# LoRa_PCB.net
KiCad netlist of a schematic drawn in Altium Designer
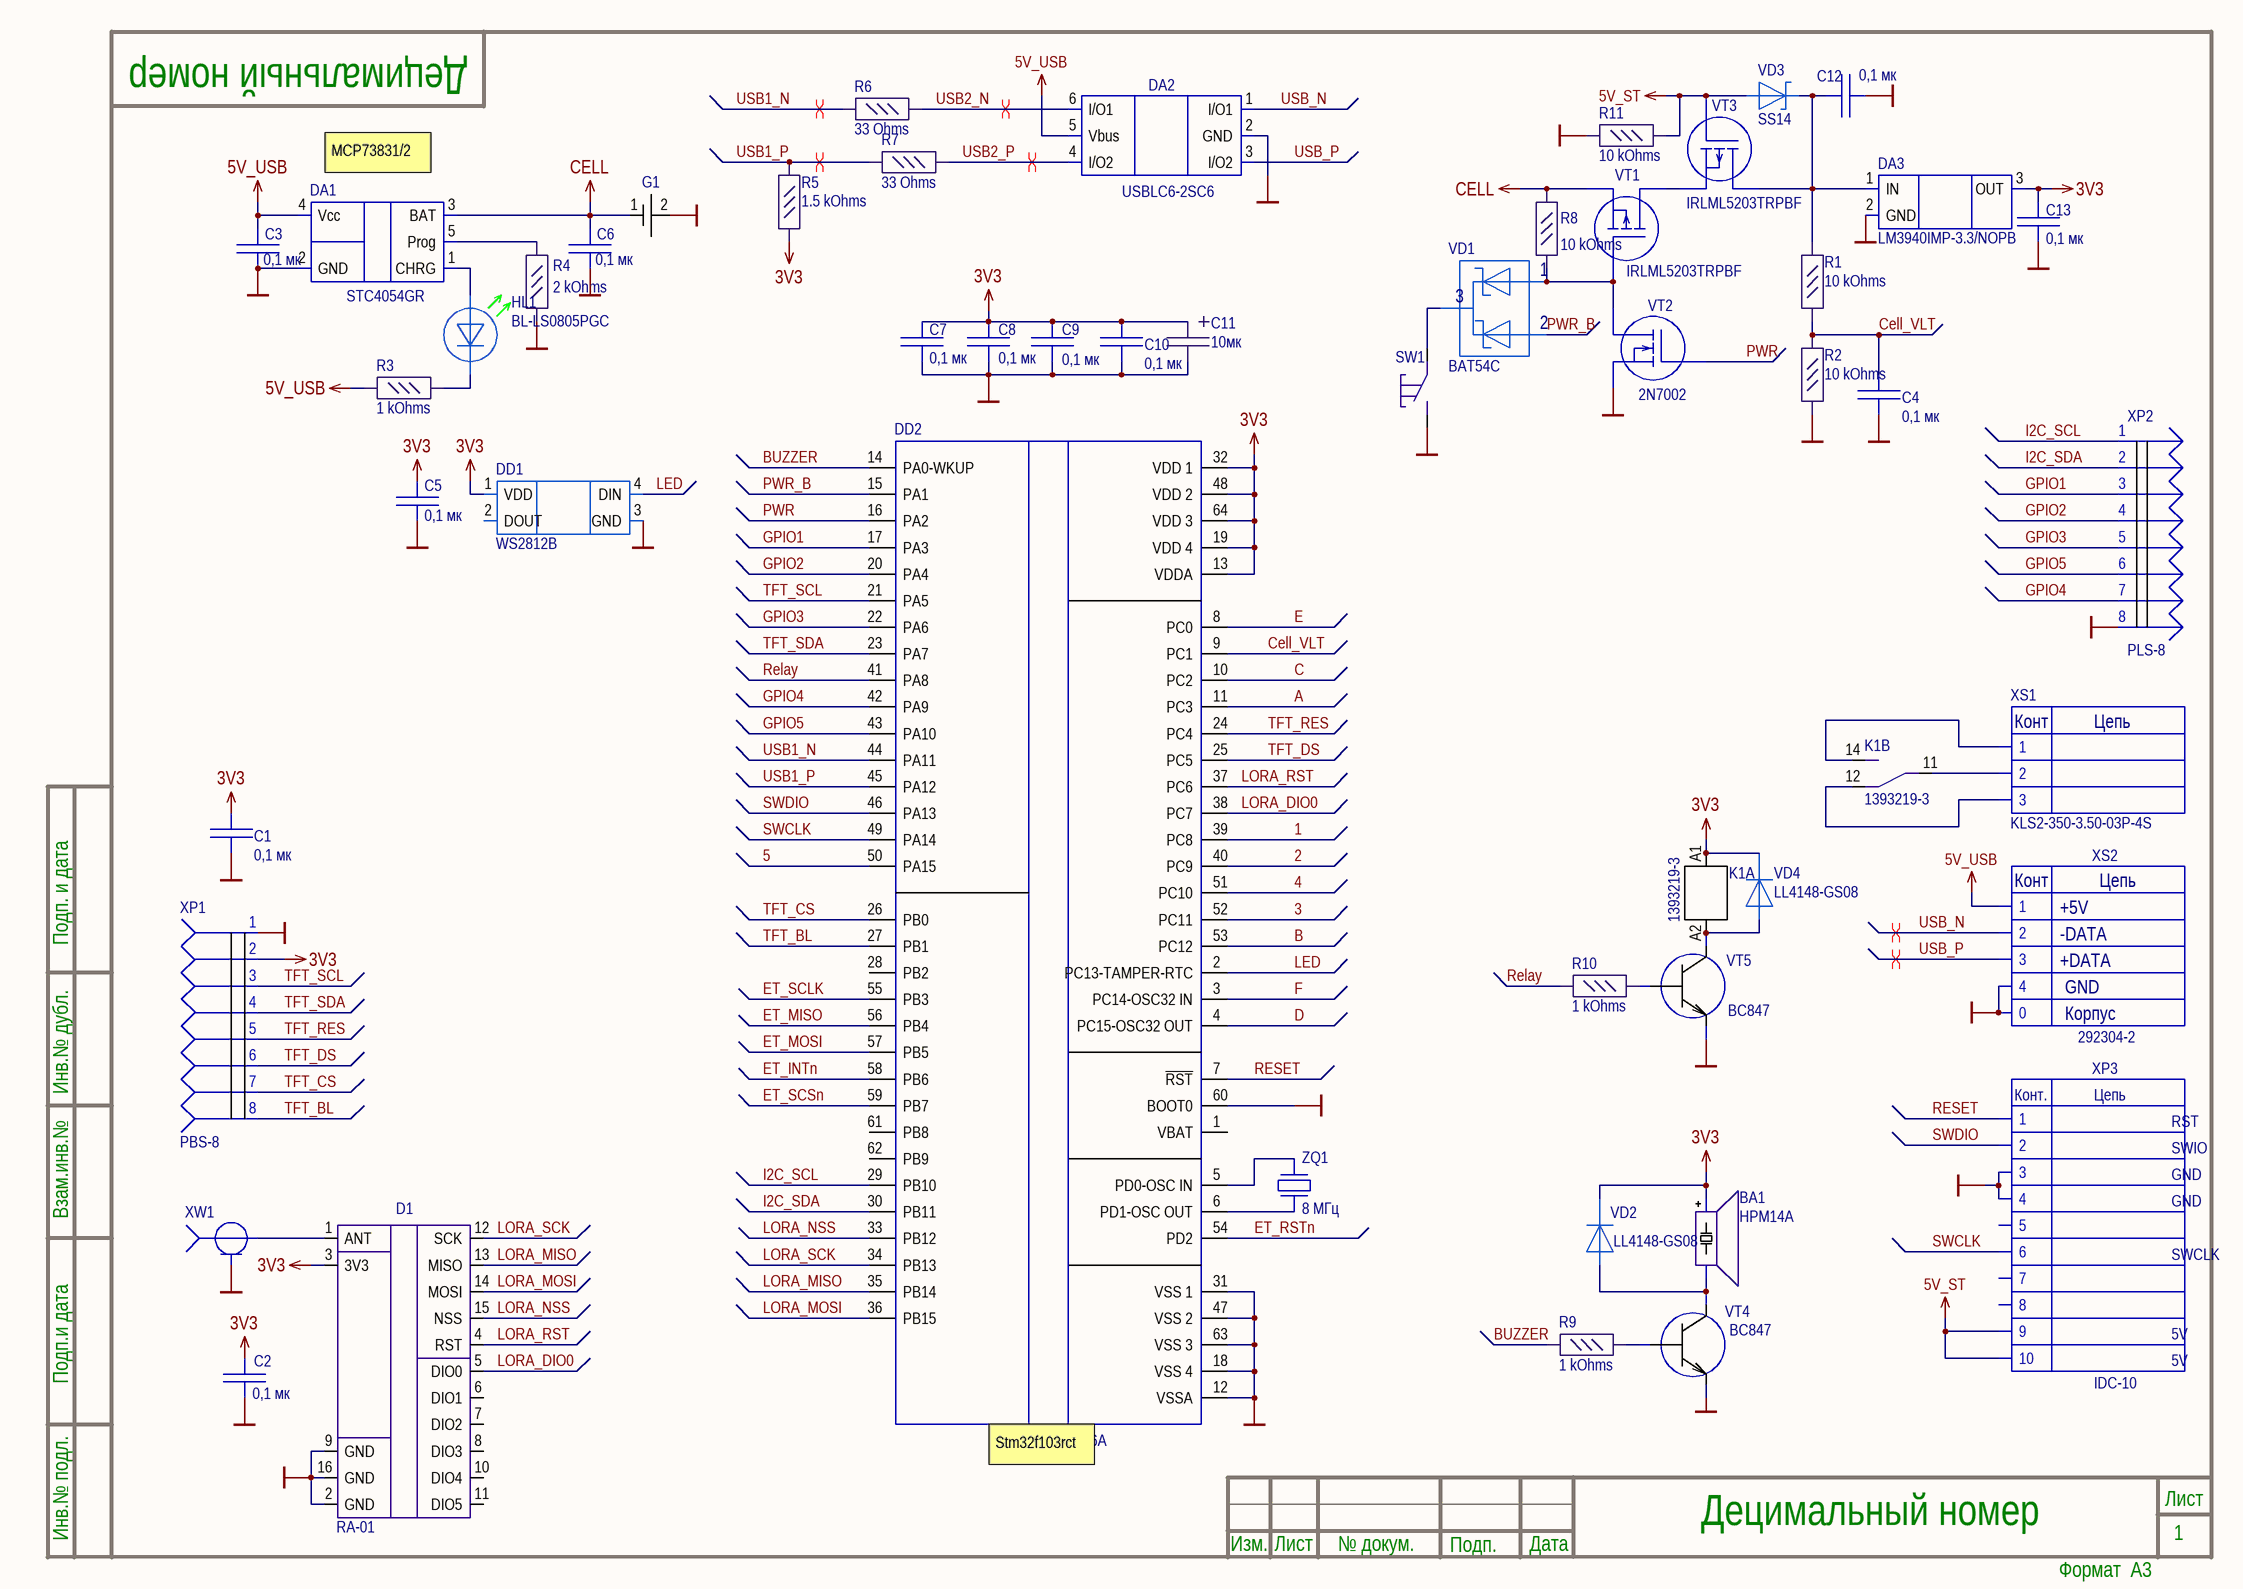
[diagram p0: LoRa_PCB.SchDoc]

(export (version "E")
  (design (tool "Eeschema 10.0.6"))
  (components
    (comp (ref "BA1") (value "HPM14A") (footprint "HPM14A") (libsource (lib "8. Other") (part "HPM14A")))
    (comp (ref "C1") (value "0,1 мк") (footprint "C_0805") (libsource (lib "RK3AZB") (part "C_0805")))
    (comp (ref "C2") (value "0,1 мк") (footprint "C_0805") (libsource (lib "RK3AZB") (part "C_0805")))
    (comp (ref "C3") (value "0,1 мк") (footprint "C_0805") (libsource (lib "2.Capasitors") (part "C_0805")))
    (comp (ref "C4") (value "0,1 мк") (footprint "C_0805") (libsource (lib "RK3AZB") (part "C_0805")))
    (comp (ref "C5") (value "0,1 мк") (footprint "C_0805") (libsource (lib "RK3AZB") (part "C_0805")))
    (comp (ref "C6") (value "0,1 мк") (footprint "C_0805") (libsource (lib "2.Capasitors") (part "C_0805")))
    (comp (ref "C7") (value "0,1 мк") (footprint "C_0805") (libsource (lib "2.Capasitors") (part "C_0805")))
    (comp (ref "C8") (value "0,1 мк") (footprint "C_0805") (libsource (lib "2.Capasitors") (part "C_0805")))
    (comp (ref "C9") (value "0,1 мк") (footprint "C_0805") (libsource (lib "2.Capasitors") (part "C_0805")))
    (comp (ref "C10") (value "0,1 мк") (footprint "C_0805") (libsource (lib "2.Capasitors") (part "C_0805")))
    (comp (ref "C11")
      (value "10мк")
      (footprint "D_CASE")
      (description "CAP TANT 10UF 10% 35V 2917")
      (fields (field (name "PART NUMBER") "T491D106K035AT") (field (name "MANUFACTURER") "KEMET"))
      (libsource (lib "Database_Lib") (part "Tantalum Capacitor"))
    )
    (comp (ref "C12") (value "0,1 мк") (footprint "C_0805") (libsource (lib "2.Capasitors") (part "C_0805")))
    (comp (ref "C13") (value "0,1 мк") (footprint "C_0805") (libsource (lib "2.Capasitors") (part "C_0805")))
    (comp (ref "D1")
      (value "RA-01")
      (footprint "RA-02")
      (description "LoRa modem")
      (libsource (lib "8. Other") (part "RA-01"))
    )
    (comp (ref "DA1")
      (value "STC4054GR")
      (footprint "TSOT23-5L")
      (description "Контроллер заряда Lion батарей")
      (libsource (lib "6.Chips") (part "STC4054GR"))
    )
    (comp (ref "DA2")
      (value "USBLC6-2SC6")
      (footprint "SOT-23-6")
      (libsource (lib "2. Chips") (part "USBLC6-2SC6"))
    )
    (comp (ref "DA3")
      (value "LM3940IMP-3.3/NOPB")
      (footprint "SOT223")
      (description "Регулятор с малым падением напряжения, преобразование 5В в 3.3В/ 1А")
      (libsource (lib "6.Chips") (part "LM3940IMP-3.3/NOPB"))
    )
    (comp (ref "DD1") (value "WS2812B") (footprint "WS2812B") (libsource (lib "4.Diodes") (part "WS2812B")))
    (comp (ref "DD2")
      (value "STM32F103R6T6A")
      (footprint "LQFP64")
      (description "32-Bit 72MHz 32KB (32K x 8) FLASH 64-LQFP")
      (libsource (lib "6.Chips") (part "STM32F103R6T6A"))
    )
    (comp (ref "G1")
      (value "12BHC186P1-GR")
      (footprint "12BHC186P1-GR")
      (description "Батарейный отсек 1x18650")
      (libsource (lib "8. Other") (part "12BHC186P1-GR"))
    )
    (comp (ref "HL1")
      (value "BL-LS0805PGC")
      (footprint "LED_0805_GREEN")
      (libsource (lib "4.Diodes") (part "BL-LS0805PGC"))
    )
    (comp (ref "K1")
      (value "1393219-3")
      (footprint "1393219-3")
      (description "Реле 5VDC")
      (libsource (lib "9.Commutation") (part "1393219-3"))
    )
    (comp (ref "R1")
      (value "10 kOhms")
      (footprint "R_0805")
      (description "RES SMD 10K OHM 1% 1/8W 0805")
      (fields (field (name "PART NUMBER") "CR0805-FX-1002ELF") (field (name "MANUFACTURER") "Bourns Inc."))
      (libsource (lib "Database_Lib") (part "Resistor"))
    )
    (comp (ref "R2")
      (value "10 kOhms")
      (footprint "R_0805")
      (description "RES SMD 10K OHM 1% 1/8W 0805")
      (fields (field (name "PART NUMBER") "CR0805-FX-1002ELF") (field (name "MANUFACTURER") "Bourns Inc."))
      (libsource (lib "Database_Lib") (part "Resistor"))
    )
    (comp (ref "R3")
      (value "1 kOhms")
      (footprint "R_0805")
      (description "RES SMD 1K OHM 1% 1/8W 0805")
      (fields (field (name "PART NUMBER") "CR0805-FX-1001ELF") (field (name "MANUFACTURER") "Bourns Inc."))
      (libsource (lib "Database_Lib") (part "Resistor"))
    )
    (comp (ref "R4")
      (value "2 kOhms")
      (footprint "R_0805")
      (description "RES SMD 2K OHM 1% 1/8W 0805")
      (fields (field (name "PART NUMBER") "CR0805-FX-2001ELF") (field (name "MANUFACTURER") "Bourns Inc."))
      (libsource (lib "Database_Lib") (part "Resistor"))
    )
    (comp (ref "R5")
      (value "1.5 kOhms")
      (footprint "R_0805")
      (description "RES SMD 1.5K OHM 1% 1/8W 0805")
      (fields (field (name "PART NUMBER") "CR0805-FX-1501ELF") (field (name "MANUFACTURER") "Bourns Inc."))
      (libsource (lib "Database_Lib") (part "Resistor"))
    )
    (comp (ref "R6")
      (value "33 Ohms")
      (footprint "R_0805")
      (description "RES SMD 33 OHM 1% 1/8W 0805")
      (fields (field (name "PART NUMBER") "CR0805-FX-33R0ELF") (field (name "MANUFACTURER") "Bourns Inc."))
      (libsource (lib "Database_Lib") (part "Resistor"))
    )
    (comp (ref "R7")
      (value "33 Ohms")
      (footprint "R_0805")
      (description "RES SMD 33 OHM 1% 1/8W 0805")
      (fields (field (name "PART NUMBER") "CR0805-FX-33R0ELF") (field (name "MANUFACTURER") "Bourns Inc."))
      (libsource (lib "Database_Lib") (part "Resistor"))
    )
    (comp (ref "R8")
      (value "10 kOhms")
      (footprint "R_0805")
      (description "RES SMD 10K OHM 1% 1/8W 0805")
      (fields (field (name "PART NUMBER") "CR0805-FX-1002ELF") (field (name "MANUFACTURER") "Bourns Inc."))
      (libsource (lib "Database_Lib") (part "Resistor"))
    )
    (comp (ref "R9")
      (value "1 kOhms")
      (footprint "R_0805")
      (description "RES SMD 1K OHM 1% 1/8W 0805")
      (fields (field (name "PART NUMBER") "CR0805-FX-1001ELF") (field (name "MANUFACTURER") "Bourns Inc."))
      (libsource (lib "Database_Lib") (part "Resistor"))
    )
    (comp (ref "R10")
      (value "1 kOhms")
      (footprint "R_0805")
      (description "RES SMD 1K OHM 1% 1/8W 0805")
      (fields (field (name "PART NUMBER") "CR0805-FX-1001ELF") (field (name "MANUFACTURER") "Bourns Inc."))
      (libsource (lib "Database_Lib") (part "Resistor"))
    )
    (comp (ref "R11")
      (value "10 kOhms")
      (footprint "R_0805")
      (description "RES SMD 10K OHM 1% 1/8W 0805")
      (fields (field (name "PART NUMBER") "CR0805-FX-1002ELF") (field (name "MANUFACTURER") "Bourns Inc."))
      (libsource (lib "Database_Lib") (part "Resistor"))
    )
    (comp (ref "SW1")
      (value "KLS7-TS6604")
      (footprint "KLS7-TS6604-5.0-180-B")
      (libsource (lib "9.Commutation") (part "KLS7-TS6604"))
    )
    (comp (ref "VD1")
      (value "BAT54C")
      (footprint "SOT23")
      (description "Диод Шоттки, 2 диода, общий катод, 30В, 0.2А [SOT-23]")
      (libsource (lib "4.Diodes") (part "BAT54C"))
    )
    (comp (ref "VD2")
      (value "LL4148-GS08")
      (footprint "SOD-80")
      (description "Диод")
      (libsource (lib "RK3AZB") (part "LL4148-GS08"))
    )
    (comp (ref "VD3") (value "SS14") (footprint "DO-214AC") (libsource (lib "4.Diodes") (part "SS14")))
    (comp (ref "VD4")
      (value "LL4148-GS08")
      (footprint "SOD-80")
      (description "Диод")
      (libsource (lib "RK3AZB") (part "LL4148-GS08"))
    )
    (comp (ref "VT1")
      (value "IRLML5203TRPBF")
      (footprint "SOT23")
      (description "Транзистор, P-канал 30В 3A logic")
      (libsource (lib "5.Transistors") (part "IRLML5203TRPBF"))
    )
    (comp (ref "VT2")
      (value "2N7002")
      (footprint "SOT23")
      (description "N-ch MFE transistor")
      (libsource (lib "5.Transistors") (part "2N7002"))
    )
    (comp (ref "VT3")
      (value "IRLML5203TRPBF")
      (footprint "SOT23")
      (description "Транзистор, P-канал 30В 3A logic")
      (libsource (lib "5.Transistors") (part "IRLML5203TRPBF"))
    )
    (comp (ref "VT4") (value "BC847") (footprint "SOT23") (libsource (lib "4. Transistors") (part "BC847")))
    (comp (ref "VT5") (value "BC847") (footprint "SOT23") (libsource (lib "RK3AZB") (part "BC847")))
    (comp (ref "XP1") (value "PBS-8") (footprint "PBS-8") (libsource (lib "7.Connectors") (part "PBS-8")))
    (comp (ref "XP2") (value "PLS-8") (footprint "PLS-8") (libsource (lib "7.Connectors") (part "PLS-8")))
    (comp (ref "XP3") (value "IDC-10") (footprint "IDC-10") (libsource (lib "7. Connectors") (part "IDC-10")))
    (comp (ref "XS1")
      (value "KLS2-350-3.50-03P-4S")
      (footprint "KLS2-350-3.50-03P-4S")
      (description "Клеммник, 3-контактный, 3.5мм")
      (libsource (lib "7. Connectors") (part "KLS2-350-3.50-03P-4S"))
    )
    (comp (ref "XS2")
      (value "292304-2")
      (footprint "USB-B")
      (libsource (lib "7.Connectors") (part "292304-2"))
    )
    (comp (ref "XW1")
      (value "HYR-1139-RP")
      (footprint "SMA (HYR1139)")
      (libsource (lib "7. Connectors") (part "HYR-1139-RP"))
    )
    (comp (ref "ZQ1")
      (value "8 МГц")
      (footprint "MJ CRYSTAL")
      (libsource (lib "8.Resonarors") (part "NX5032GA-8MHz"))
    )
  )
  (nets
    (net (code "1") (name "/1") (class "Default")
      (node (ref "DD2") (pin "39") (pinfunction "PC8_39") (pintype "passive"))
    )
    (net (code "2") (name "/2") (class "Default")
      (node (ref "DD2") (pin "40") (pinfunction "PC9_40") (pintype "passive"))
    )
    (net (code "3") (name "/3") (class "Default")
      (node (ref "DD2") (pin "52") (pinfunction "PC11_52") (pintype "passive"))
    )
    (net (code "4") (name "/4") (class "Default")
      (node (ref "DD2") (pin "51") (pinfunction "PC10_51") (pintype "passive"))
    )
    (net (code "5") (name "/5") (class "Default")
      (node (ref "DD2") (pin "50") (pinfunction "PA15_50") (pintype "passive"))
    )
    (net (code "6") (name "/A") (class "Default")
      (node (ref "DD2") (pin "11") (pinfunction "PC3_11") (pintype "passive"))
    )
    (net (code "7") (name "/B") (class "Default")
      (node (ref "DD2") (pin "53") (pinfunction "PC12_53") (pintype "passive"))
    )
    (net (code "8") (name "/BUZZER") (class "Default")
      (node (ref "DD2") (pin "14") (pinfunction "PA0-WKUP_14") (pintype "passive"))
      (node (ref "R9") (pin "2") (pinfunction "2_2") (pintype "passive"))
    )
    (net (code "9") (name "/C") (class "Default")
      (node (ref "DD2") (pin "10") (pinfunction "PC2_10") (pintype "passive"))
    )
    (net (code "10") (name "/Cell_VLT") (class "Default")
      (node (ref "C4") (pin "2") (pinfunction "2_2") (pintype "passive"))
      (node (ref "DD2") (pin "9") (pinfunction "PC1_9") (pintype "passive"))
      (node (ref "R1") (pin "2") (pinfunction "2_2") (pintype "passive"))
      (node (ref "R2") (pin "1") (pinfunction "1_1") (pintype "passive"))
    )
    (net (code "11") (name "/D") (class "Default")
      (node (ref "DD2") (pin "4") (pinfunction "PC15-OSC32_OUT_4") (pintype "passive"))
    )
    (net (code "12") (name "/E") (class "Default")
      (node (ref "DD2") (pin "8") (pinfunction "PC0_8") (pintype "passive"))
    )
    (net (code "13") (name "/ET_INTn") (class "Default")
      (node (ref "DD2") (pin "58") (pinfunction "PB6_58") (pintype "passive"))
    )
    (net (code "14") (name "/ET_MISO") (class "Default")
      (node (ref "DD2") (pin "56") (pinfunction "PB4_56") (pintype "passive"))
    )
    (net (code "15") (name "/ET_MOSI") (class "Default")
      (node (ref "DD2") (pin "57") (pinfunction "PB5_57") (pintype "passive"))
    )
    (net (code "16") (name "/ET_RSTn") (class "Default")
      (node (ref "DD2") (pin "54") (pinfunction "PD2_54") (pintype "passive"))
    )
    (net (code "17") (name "/ET_SCLK") (class "Default")
      (node (ref "DD2") (pin "55") (pinfunction "PB3_55") (pintype "passive"))
    )
    (net (code "18") (name "/ET_SCSn") (class "Default")
      (node (ref "DD2") (pin "59") (pinfunction "PB7_59") (pintype "passive"))
    )
    (net (code "19") (name "/F") (class "Default")
      (node (ref "DD2") (pin "3") (pinfunction "PC14-OSC32_IN_3") (pintype "passive"))
    )
    (net (code "20") (name "/GPIO1") (class "Default")
      (node (ref "DD2") (pin "17") (pinfunction "PA3_17") (pintype "passive"))
      (node (ref "XP2") (pin "3") (pinfunction "3_3") (pintype "passive"))
    )
    (net (code "21") (name "/GPIO2") (class "Default")
      (node (ref "DD2") (pin "20") (pinfunction "PA4_20") (pintype "passive"))
      (node (ref "XP2") (pin "4") (pinfunction "4_4") (pintype "passive"))
    )
    (net (code "22") (name "/GPIO3") (class "Default")
      (node (ref "DD2") (pin "22") (pinfunction "PA6_22") (pintype "passive"))
      (node (ref "XP2") (pin "5") (pinfunction "5_5") (pintype "passive"))
    )
    (net (code "23") (name "/GPIO4") (class "Default")
      (node (ref "DD2") (pin "42") (pinfunction "PA9_42") (pintype "passive"))
      (node (ref "XP2") (pin "7") (pinfunction "7_7") (pintype "passive"))
    )
    (net (code "24") (name "/GPIO5") (class "Default")
      (node (ref "DD2") (pin "43") (pinfunction "PA10_43") (pintype "passive"))
      (node (ref "XP2") (pin "6") (pinfunction "6_6") (pintype "passive"))
    )
    (net (code "25") (name "/I2C_SCL") (class "Default")
      (node (ref "DD2") (pin "29") (pinfunction "PB10_29") (pintype "passive"))
      (node (ref "XP2") (pin "1") (pinfunction "1_1") (pintype "passive"))
    )
    (net (code "26") (name "/I2C_SDA") (class "Default")
      (node (ref "DD2") (pin "30") (pinfunction "PB11_30") (pintype "passive"))
      (node (ref "XP2") (pin "2") (pinfunction "2_2") (pintype "passive"))
    )
    (net (code "27") (name "/LED") (class "Default")
      (node (ref "DD1") (pin "4") (pinfunction "DIN_4") (pintype "passive"))
      (node (ref "DD2") (pin "2") (pinfunction "PC13-TAMPER-RTC_2") (pintype "passive"))
    )
    (net (code "28") (name "/LORA_DIO0") (class "Default")
      (node (ref "D1") (pin "5") (pinfunction "DIO0_5") (pintype "passive"))
      (node (ref "DD2") (pin "38") (pinfunction "PC7_38") (pintype "passive"))
    )
    (net (code "29") (name "/LORA_MISO") (class "Default")
      (node (ref "D1") (pin "13") (pinfunction "MISO_13") (pintype "passive"))
      (node (ref "DD2") (pin "35") (pinfunction "PB14_35") (pintype "passive"))
    )
    (net (code "30") (name "/LORA_MOSI") (class "Default")
      (node (ref "D1") (pin "14") (pinfunction "MOSI_14") (pintype "passive"))
      (node (ref "DD2") (pin "36") (pinfunction "PB15_36") (pintype "passive"))
    )
    (net (code "31") (name "/LORA_NSS") (class "Default")
      (node (ref "D1") (pin "15") (pinfunction "NSS_15") (pintype "passive"))
      (node (ref "DD2") (pin "33") (pinfunction "PB12_33") (pintype "passive"))
    )
    (net (code "32") (name "/LORA_RST") (class "Default")
      (node (ref "D1") (pin "4") (pinfunction "RST_4") (pintype "passive"))
      (node (ref "DD2") (pin "37") (pinfunction "PC6_37") (pintype "passive"))
    )
    (net (code "33") (name "/LORA_SCK") (class "Default")
      (node (ref "D1") (pin "12") (pinfunction "SCK_12") (pintype "passive"))
      (node (ref "DD2") (pin "34") (pinfunction "PB13_34") (pintype "passive"))
    )
    (net (code "34") (name "/PWR") (class "Default")
      (node (ref "DD2") (pin "16") (pinfunction "PA2_16") (pintype "passive"))
      (node (ref "VT2") (pin "1") (pinfunction "G_1") (pintype "passive"))
    )
    (net (code "35") (name "/PWR_B") (class "Default")
      (node (ref "DD2") (pin "15") (pinfunction "PA1_15") (pintype "passive"))
      (node (ref "VD1") (pin "2") (pinfunction "C2_2") (pintype "passive"))
    )
    (net (code "36") (name "/RESET") (class "Default")
      (node (ref "DD2") (pin "7") (pinfunction "~{RST}_7") (pintype "passive"))
      (node (ref "XP3") (pin "1") (pinfunction "1_1") (pintype "passive"))
    )
    (net (code "37") (name "/Relay") (class "Default")
      (node (ref "DD2") (pin "41") (pinfunction "PA8_41") (pintype "passive"))
      (node (ref "R10") (pin "2") (pinfunction "2_2") (pintype "passive"))
    )
    (net (code "38") (name "/SWCLK") (class "Default")
      (node (ref "DD2") (pin "49") (pinfunction "PA14_49") (pintype "passive"))
      (node (ref "XP3") (pin "6") (pinfunction "6_6") (pintype "passive"))
    )
    (net (code "39") (name "/SWDIO") (class "Default")
      (node (ref "DD2") (pin "46") (pinfunction "PA13_46") (pintype "passive"))
      (node (ref "XP3") (pin "2") (pinfunction "2_2") (pintype "passive"))
    )
    (net (code "40") (name "/TFT_BL") (class "Default")
      (node (ref "DD2") (pin "27") (pinfunction "PB1_27") (pintype "passive"))
      (node (ref "XP1") (pin "8") (pinfunction "8_8") (pintype "passive"))
    )
    (net (code "41") (name "/TFT_CS") (class "Default")
      (node (ref "DD2") (pin "26") (pinfunction "PB0_26") (pintype "passive"))
      (node (ref "XP1") (pin "7") (pinfunction "7_7") (pintype "passive"))
    )
    (net (code "42") (name "/TFT_DS") (class "Default")
      (node (ref "DD2") (pin "25") (pinfunction "PC5_25") (pintype "passive"))
      (node (ref "XP1") (pin "6") (pinfunction "6_6") (pintype "passive"))
    )
    (net (code "43") (name "/TFT_RES") (class "Default")
      (node (ref "DD2") (pin "24") (pinfunction "PC4_24") (pintype "passive"))
      (node (ref "XP1") (pin "5") (pinfunction "5_5") (pintype "passive"))
    )
    (net (code "44") (name "/TFT_SCL") (class "Default")
      (node (ref "DD2") (pin "21") (pinfunction "PA5_21") (pintype "passive"))
      (node (ref "XP1") (pin "3") (pinfunction "3_3") (pintype "passive"))
    )
    (net (code "45") (name "/TFT_SDA") (class "Default")
      (node (ref "DD2") (pin "23") (pinfunction "PA7_23") (pintype "passive"))
      (node (ref "XP1") (pin "4") (pinfunction "4_4") (pintype "passive"))
    )
    (net (code "46") (name "/USB1_N") (class "Default")
      (node (ref "DD2") (pin "44") (pinfunction "PA11_44") (pintype "passive"))
      (node (ref "R6") (pin "1") (pinfunction "1_1") (pintype "passive"))
    )
    (net (code "47") (name "/USB1_P") (class "Default")
      (node (ref "DD2") (pin "45") (pinfunction "PA12_45") (pintype "passive"))
      (node (ref "R5") (pin "2") (pinfunction "2_2") (pintype "passive"))
      (node (ref "R7") (pin "1") (pinfunction "1_1") (pintype "passive"))
    )
    (net (code "48") (name "/USB2_N") (class "Default")
      (node (ref "DA2") (pin "6") (pinfunction "I/O1_6") (pintype "passive"))
      (node (ref "R6") (pin "2") (pinfunction "2_2") (pintype "passive"))
    )
    (net (code "49") (name "/USB2_P") (class "Default")
      (node (ref "DA2") (pin "4") (pinfunction "I/O2_4") (pintype "passive"))
      (node (ref "R7") (pin "2") (pinfunction "2_2") (pintype "passive"))
    )
    (net (code "50") (name "/USB_N") (class "Default")
      (node (ref "DA2") (pin "1") (pinfunction "I/O1_1") (pintype "passive"))
      (node (ref "XS2") (pin "2") (pinfunction "2_2") (pintype "passive"))
    )
    (net (code "51") (name "/USB_P") (class "Default")
      (node (ref "DA2") (pin "3") (pinfunction "I/O2_3") (pintype "passive"))
      (node (ref "XS2") (pin "3") (pinfunction "3_3") (pintype "passive"))
    )
    (net (code "52") (name "3V3") (class "Default")
      (node (ref "BA1") (pin "1") (pinfunction "1_1") (pintype "passive"))
      (node (ref "C1") (pin "2") (pinfunction "2_2") (pintype "passive"))
      (node (ref "C10") (pin "2") (pinfunction "2_2") (pintype "passive"))
      (node (ref "C11") (pin "1") (pinfunction "1_1") (pintype "passive"))
      (node (ref "C13") (pin "2") (pinfunction "2_2") (pintype "passive"))
      (node (ref "C2") (pin "2") (pinfunction "2_2") (pintype "passive"))
      (node (ref "C5") (pin "2") (pinfunction "2_2") (pintype "passive"))
      (node (ref "C7") (pin "2") (pinfunction "2_2") (pintype "passive"))
      (node (ref "C8") (pin "2") (pinfunction "2_2") (pintype "passive"))
      (node (ref "C9") (pin "2") (pinfunction "2_2") (pintype "passive"))
      (node (ref "D1") (pin "3") (pinfunction "3V3_3") (pintype "passive"))
      (node (ref "DA3") (pin "3") (pinfunction "OUT_3") (pintype "passive"))
      (node (ref "DD1") (pin "1") (pinfunction "VDD_1") (pintype "passive"))
      (node (ref "DD2") (pin "13") (pinfunction "VDDA_13") (pintype "power_in"))
      (node (ref "DD2") (pin "19") (pinfunction "VDD_4_19") (pintype "power_in"))
      (node (ref "DD2") (pin "32") (pinfunction "VDD_1_32") (pintype "power_in"))
      (node (ref "DD2") (pin "48") (pinfunction "VDD_2_48") (pintype "power_in"))
      (node (ref "DD2") (pin "64") (pinfunction "VDD_3_64") (pintype "power_in"))
      (node (ref "K1") (pin "A1") (pinfunction "1_A1") (pintype "passive"))
      (node (ref "R5") (pin "1") (pinfunction "1_1") (pintype "passive"))
      (node (ref "VD2") (pin "2") (pinfunction "2_2") (pintype "passive"))
      (node (ref "VD4") (pin "2") (pinfunction "2_2") (pintype "passive"))
      (node (ref "XP1") (pin "2") (pinfunction "2_2") (pintype "passive"))
    )
    (net (code "53") (name "5V_ST") (class "Default")
      (node (ref "R11") (pin "1") (pinfunction "1_1") (pintype "passive"))
      (node (ref "VD3") (pin "1") (pinfunction "1_1") (pintype "passive"))
      (node (ref "VT3") (pin "1") (pinfunction "G_1") (pintype "passive"))
      (node (ref "XP3") (pin "10") (pinfunction "10_10") (pintype "passive"))
      (node (ref "XP3") (pin "9") (pinfunction "9_9") (pintype "passive"))
    )
    (net (code "54") (name "5V_USB") (class "Default")
      (node (ref "C3") (pin "2") (pinfunction "2_2") (pintype "passive"))
      (node (ref "DA1") (pin "4") (pinfunction "Vcc_4") (pintype "passive"))
      (node (ref "DA2") (pin "5") (pinfunction "Vbus_5") (pintype "passive"))
      (node (ref "R3") (pin "2") (pinfunction "2_2") (pintype "passive"))
      (node (ref "XS2") (pin "1") (pinfunction "1_1") (pintype "passive"))
    )
    (net (code "55") (name "CELL") (class "Default")
      (node (ref "C6") (pin "2") (pinfunction "2_2") (pintype "passive"))
      (node (ref "DA1") (pin "3") (pinfunction "BAT_3") (pintype "passive"))
      (node (ref "G1") (pin "1") (pinfunction "1_1") (pintype "passive"))
      (node (ref "R8") (pin "2") (pinfunction "2_2") (pintype "passive"))
      (node (ref "VT1") (pin "2") (pinfunction "S_2") (pintype "passive"))
    )
    (net (code "56") (name "GND") (class "Default")
      (node (ref "C1") (pin "1") (pinfunction "1_1") (pintype "passive"))
      (node (ref "C10") (pin "1") (pinfunction "1_1") (pintype "passive"))
      (node (ref "C11") (pin "2") (pinfunction "2_2") (pintype "passive"))
      (node (ref "C12") (pin "2") (pinfunction "2_2") (pintype "passive"))
      (node (ref "C13") (pin "1") (pinfunction "1_1") (pintype "passive"))
      (node (ref "C2") (pin "1") (pinfunction "1_1") (pintype "passive"))
      (node (ref "C3") (pin "1") (pinfunction "1_1") (pintype "passive"))
      (node (ref "C4") (pin "1") (pinfunction "1_1") (pintype "passive"))
      (node (ref "C5") (pin "1") (pinfunction "1_1") (pintype "passive"))
      (node (ref "C6") (pin "1") (pinfunction "1_1") (pintype "passive"))
      (node (ref "C7") (pin "1") (pinfunction "1_1") (pintype "passive"))
      (node (ref "C8") (pin "1") (pinfunction "1_1") (pintype "passive"))
      (node (ref "C9") (pin "1") (pinfunction "1_1") (pintype "passive"))
      (node (ref "D1") (pin "16") (pinfunction "GND_16") (pintype "passive"))
      (node (ref "D1") (pin "2") (pinfunction "GND_2") (pintype "passive"))
      (node (ref "D1") (pin "9") (pinfunction "GND_9") (pintype "passive"))
      (node (ref "DA1") (pin "2") (pinfunction "GND_2") (pintype "passive"))
      (node (ref "DA2") (pin "2") (pinfunction "GND_2") (pintype "passive"))
      (node (ref "DA3") (pin "2") (pinfunction "GND_2") (pintype "passive"))
      (node (ref "DD1") (pin "3") (pinfunction "GND_3") (pintype "passive"))
      (node (ref "DD2") (pin "12") (pinfunction "VSSA_12") (pintype "power_in"))
      (node (ref "DD2") (pin "18") (pinfunction "VSS_4_18") (pintype "power_in"))
      (node (ref "DD2") (pin "31") (pinfunction "VSS_1_31") (pintype "power_in"))
      (node (ref "DD2") (pin "47") (pinfunction "VSS_2_47") (pintype "power_in"))
      (node (ref "DD2") (pin "60") (pinfunction "BOOT0_60") (pintype "passive"))
      (node (ref "DD2") (pin "63") (pinfunction "VSS_3_63") (pintype "power_in"))
      (node (ref "G1") (pin "2") (pinfunction "2_2") (pintype "passive"))
      (node (ref "R11") (pin "2") (pinfunction "2_2") (pintype "passive"))
      (node (ref "R2") (pin "2") (pinfunction "2_2") (pintype "passive"))
      (node (ref "R4") (pin "1") (pinfunction "1_1") (pintype "passive"))
      (node (ref "SW1") (pin "1") (pinfunction "1_1") (pintype "passive"))
      (node (ref "VT2") (pin "2") (pinfunction "S_2") (pintype "passive"))
      (node (ref "VT4") (pin "2") (pinfunction "E_2") (pintype "passive"))
      (node (ref "VT5") (pin "2") (pinfunction "E_2") (pintype "passive"))
      (node (ref "XP1") (pin "1") (pinfunction "1_1") (pintype "passive"))
      (node (ref "XP2") (pin "8") (pinfunction "8_8") (pintype "passive"))
      (node (ref "XP3") (pin "3") (pinfunction "3_3") (pintype "passive"))
      (node (ref "XP3") (pin "4") (pinfunction "4_4") (pintype "passive"))
      (node (ref "XS2") (pin "0") (pinfunction "0_0") (pintype "passive"))
      (node (ref "XS2") (pin "4") (pinfunction "4_4") (pintype "passive"))
      (node (ref "XW1") (pin "1") (pinfunction "1_1") (pintype "passive"))
    )
    (net (code "57") (name "Net-(D1-ANT)") (class "Default")
      (node (ref "D1") (pin "1") (pinfunction "ANT_1") (pintype "passive"))
      (node (ref "XW1") (pin "2") (pinfunction "2_2") (pintype "passive"))
    )
    (net (code "58") (name "Net-(DA1-CHRG)") (class "Default")
      (node (ref "DA1") (pin "1") (pinfunction "CHRG_1") (pintype "passive"))
      (node (ref "HL1") (pin "1") (pinfunction "1_1") (pintype "passive"))
    )
    (net (code "59") (name "Net-(DA1-Prog)") (class "Default")
      (node (ref "DA1") (pin "5") (pinfunction "Prog_5") (pintype "passive"))
      (node (ref "R4") (pin "2") (pinfunction "2_2") (pintype "passive"))
    )
    (net (code "60") (name "Net-(DA3-IN)") (class "Default")
      (node (ref "C12") (pin "1") (pinfunction "1_1") (pintype "passive"))
      (node (ref "DA3") (pin "1") (pinfunction "IN_1") (pintype "passive"))
      (node (ref "R1") (pin "1") (pinfunction "1_1") (pintype "passive"))
      (node (ref "VD3") (pin "2") (pinfunction "2_2") (pintype "passive"))
      (node (ref "VT3") (pin "3") (pinfunction "D_3") (pintype "passive"))
    )
    (net (code "61") (name "Net-(DD2-PD0-OSC_IN)") (class "Default")
      (node (ref "DD2") (pin "5") (pinfunction "PD0-OSC_IN_5") (pintype "passive"))
      (node (ref "ZQ1") (pin "3") (pinfunction "3_3") (pintype "passive"))
    )
    (net (code "62") (name "Net-(DD2-PD1-OSC_OUT)") (class "Default")
      (node (ref "DD2") (pin "6") (pinfunction "PD1-OSC_OUT_6") (pintype "passive"))
      (node (ref "ZQ1") (pin "1") (pinfunction "1_1") (pintype "passive"))
    )
    (net (code "63") (name "Net-(HL1-Pad2)") (class "Default")
      (node (ref "HL1") (pin "2") (pinfunction "2_2") (pintype "passive"))
      (node (ref "R3") (pin "1") (pinfunction "1_1") (pintype "passive"))
    )
    (net (code "64") (name "Net-(K1-Pad11)") (class "Default")
      (node (ref "K1") (pin "11") (pinfunction "11_11") (pintype "passive"))
      (node (ref "XS1") (pin "2") (pinfunction "2_2") (pintype "passive"))
    )
    (net (code "65") (name "Net-(K1-Pad12)") (class "Default")
      (node (ref "K1") (pin "12") (pinfunction "12_12") (pintype "passive"))
      (node (ref "XS1") (pin "3") (pinfunction "3_3") (pintype "passive"))
    )
    (net (code "66") (name "Net-(K1-Pad14)") (class "Default")
      (node (ref "K1") (pin "14") (pinfunction "14_14") (pintype "passive"))
      (node (ref "XS1") (pin "1") (pinfunction "1_1") (pintype "passive"))
    )
    (net (code "67") (name "Net-(K1A-2)") (class "Default")
      (node (ref "K1") (pin "A2") (pinfunction "2_A2") (pintype "passive"))
      (node (ref "VD4") (pin "1") (pinfunction "1_1") (pintype "passive"))
      (node (ref "VT5") (pin "3") (pinfunction "C_3") (pintype "passive"))
    )
    (net (code "68") (name "Net-(VD1-A1)") (class "Default")
      (node (ref "R8") (pin "1") (pinfunction "1_1") (pintype "passive"))
      (node (ref "VD1") (pin "1") (pinfunction "A1_1") (pintype "passive"))
      (node (ref "VT1") (pin "1") (pinfunction "G_1") (pintype "passive"))
      (node (ref "VT2") (pin "3") (pinfunction "D_3") (pintype "passive"))
    )
    (net (code "69") (name "Net-(VD1-C1A2)") (class "Default")
      (node (ref "SW1") (pin "2") (pinfunction "2_2") (pintype "passive"))
      (node (ref "VD1") (pin "3") (pinfunction "C1A2_3") (pintype "passive"))
    )
    (net (code "70") (name "Net-(VT1-D)") (class "Default")
      (node (ref "VT1") (pin "3") (pinfunction "D_3") (pintype "passive"))
      (node (ref "VT3") (pin "2") (pinfunction "S_2") (pintype "passive"))
    )
    (net (code "71") (name "Net-(VT4-B)") (class "Default")
      (node (ref "R9") (pin "1") (pinfunction "1_1") (pintype "passive"))
      (node (ref "VT4") (pin "1") (pinfunction "B_1") (pintype "passive"))
    )
    (net (code "72") (name "Net-(VT4-C)") (class "Default")
      (node (ref "BA1") (pin "2") (pinfunction "2_2") (pintype "passive"))
      (node (ref "VD2") (pin "1") (pinfunction "1_1") (pintype "passive"))
      (node (ref "VT4") (pin "3") (pinfunction "C_3") (pintype "passive"))
    )
    (net (code "73") (name "Net-(VT5-B)") (class "Default")
      (node (ref "R10") (pin "1") (pinfunction "1_1") (pintype "passive"))
      (node (ref "VT5") (pin "1") (pinfunction "B_1") (pintype "passive"))
    )
    (net (code "74") (name "unconnected-(D1-DIO1-Pad6)") (class "Default")
      (node (ref "D1") (pin "6") (pinfunction "DIO1_6") (pintype "passive"))
    )
    (net (code "75") (name "unconnected-(D1-DIO2-Pad7)") (class "Default")
      (node (ref "D1") (pin "7") (pinfunction "DIO2_7") (pintype "passive"))
    )
    (net (code "76") (name "unconnected-(D1-DIO3-Pad8)") (class "Default")
      (node (ref "D1") (pin "8") (pinfunction "DIO3_8") (pintype "passive"))
    )
    (net (code "77") (name "unconnected-(D1-DIO4-Pad10)") (class "Default")
      (node (ref "D1") (pin "10") (pinfunction "DIO4_10") (pintype "passive"))
    )
    (net (code "78") (name "unconnected-(D1-DIO5-Pad11)") (class "Default")
      (node (ref "D1") (pin "11") (pinfunction "DIO5_11") (pintype "passive"))
    )
    (net (code "79") (name "unconnected-(DD1-DOUT-Pad2)") (class "Default")
      (node (ref "DD1") (pin "2") (pinfunction "DOUT_2") (pintype "passive"))
    )
    (net (code "80") (name "unconnected-(DD2-PB2-Pad28)") (class "Default")
      (node (ref "DD2") (pin "28") (pinfunction "PB2_28") (pintype "passive"))
    )
    (net (code "81") (name "unconnected-(DD2-PB8-Pad61)") (class "Default")
      (node (ref "DD2") (pin "61") (pinfunction "PB8_61") (pintype "passive"))
    )
    (net (code "82") (name "unconnected-(DD2-PB9-Pad62)") (class "Default")
      (node (ref "DD2") (pin "62") (pinfunction "PB9_62") (pintype "passive"))
    )
    (net (code "83") (name "unconnected-(DD2-VBAT-Pad1)") (class "Default")
      (node (ref "DD2") (pin "1") (pinfunction "VBAT_1") (pintype "power_in"))
    )
    (net (code "84") (name "unconnected-(XP3-Pad5)") (class "Default")
      (node (ref "XP3") (pin "5") (pinfunction "5_5") (pintype "passive"))
    )
    (net (code "85") (name "unconnected-(XP3-Pad7)") (class "Default")
      (node (ref "XP3") (pin "7") (pinfunction "7_7") (pintype "passive"))
    )
    (net (code "86") (name "unconnected-(XP3-Pad8)") (class "Default")
      (node (ref "XP3") (pin "8") (pinfunction "8_8") (pintype "passive"))
    )
  )
)
